# untitled.net
KiCad netlist of a schematic drawn in EAGLE
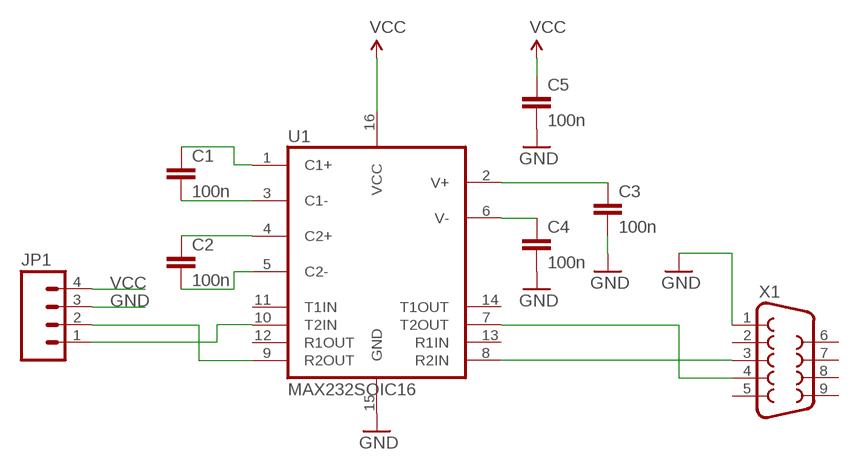
[diagram p0: schematic, sheet 1]

(export (version "E")
  (design (tool "Eeschema 10.0.6"))
  (components
    (comp (ref "C1")
      (value "100n")
      (footprint "eagle-import:1206")
      (libsource (lib "eagle-import") (part "CAP1206"))
    )
    (comp (ref "C2")
      (value "100n")
      (footprint "eagle-import:1206")
      (libsource (lib "eagle-import") (part "CAP1206"))
    )
    (comp (ref "C3")
      (value "100n")
      (footprint "eagle-import:1206")
      (libsource (lib "eagle-import") (part "CAP1206"))
    )
    (comp (ref "C4")
      (value "100n")
      (footprint "eagle-import:1206")
      (libsource (lib "eagle-import") (part "CAP1206"))
    )
    (comp (ref "C5")
      (value "100n")
      (footprint "eagle-import:1206")
      (libsource (lib "eagle-import") (part "CAP1206"))
    )
    (comp (ref "JP1")
      (value "M04PTH")
      (footprint "eagle-import:1X04")
      (libsource (lib "eagle-import") (part "M04PTH"))
    )
    (comp (ref "U1")
      (value "MAX232SOIC16")
      (footprint "eagle-import:SO016")
      (libsource (lib "eagle-import") (part "MAX232SOIC16"))
    )
    (comp (ref "X1")
      (value "DB9FEMALE")
      (footprint "eagle-import:DB9")
      (libsource (lib "eagle-import") (part "DB9FEMALE"))
    )
  )
  (nets
    (net (code "1") (name "GND") (class "Default")
      (node (ref "C3") (pin "2") (pinfunction "2_2") (pintype "passive"))
      (node (ref "C4") (pin "2") (pinfunction "2_2") (pintype "passive"))
      (node (ref "C5") (pin "2") (pinfunction "2_2") (pintype "passive"))
      (node (ref "JP1") (pin "3") (pinfunction "3_3") (pintype "passive"))
      (node (ref "U1") (pin "15") (pinfunction "GND_15") (pintype "bidirectional"))
      (node (ref "X1") (pin "1") (pinfunction "1_1") (pintype "passive"))
    )
    (net (code "2") (name "Net-(U1-C1+)") (class "Default")
      (node (ref "C1") (pin "1") (pinfunction "1_1") (pintype "passive"))
      (node (ref "U1") (pin "1") (pinfunction "C1+_1") (pintype "bidirectional"))
    )
    (net (code "3") (name "Net-(U1-C1-)") (class "Default")
      (node (ref "C1") (pin "2") (pinfunction "2_2") (pintype "passive"))
      (node (ref "U1") (pin "3") (pinfunction "C1-_3") (pintype "bidirectional"))
    )
    (net (code "4") (name "Net-(U1-C2+)") (class "Default")
      (node (ref "C2") (pin "1") (pinfunction "1_1") (pintype "passive"))
      (node (ref "U1") (pin "4") (pinfunction "C2+_4") (pintype "bidirectional"))
    )
    (net (code "5") (name "Net-(U1-C2-)") (class "Default")
      (node (ref "C2") (pin "2") (pinfunction "2_2") (pintype "passive"))
      (node (ref "U1") (pin "5") (pinfunction "C2-_5") (pintype "bidirectional"))
    )
    (net (code "6") (name "Net-(U1-R2IN)") (class "Default")
      (node (ref "U1") (pin "8") (pinfunction "R2IN_8") (pintype "input"))
      (node (ref "X1") (pin "3") (pinfunction "3_3") (pintype "passive"))
    )
    (net (code "7") (name "Net-(U1-R2OUT)") (class "Default")
      (node (ref "JP1") (pin "2") (pinfunction "2_2") (pintype "passive"))
      (node (ref "U1") (pin "9") (pinfunction "R2OUT_9") (pintype "output"))
    )
    (net (code "8") (name "Net-(U1-T2IN)") (class "Default")
      (node (ref "JP1") (pin "1") (pinfunction "1_1") (pintype "passive"))
      (node (ref "U1") (pin "10") (pinfunction "T2IN_10") (pintype "input"))
    )
    (net (code "9") (name "Net-(U1-T2OUT)") (class "Default")
      (node (ref "U1") (pin "7") (pinfunction "T2OUT_7") (pintype "output"))
      (node (ref "X1") (pin "4") (pinfunction "4_4") (pintype "passive"))
    )
    (net (code "10") (name "Net-(U1-V+)") (class "Default")
      (node (ref "C3") (pin "1") (pinfunction "1_1") (pintype "passive"))
      (node (ref "U1") (pin "2") (pinfunction "V+_2") (pintype "bidirectional"))
    )
    (net (code "11") (name "Net-(U1-V-)") (class "Default")
      (node (ref "C4") (pin "1") (pinfunction "1_1") (pintype "passive"))
      (node (ref "U1") (pin "6") (pinfunction "V-_6") (pintype "bidirectional"))
    )
    (net (code "12") (name "VCC") (class "Default")
      (node (ref "C5") (pin "1") (pinfunction "1_1") (pintype "passive"))
      (node (ref "JP1") (pin "4") (pinfunction "4_4") (pintype "passive"))
      (node (ref "U1") (pin "16") (pinfunction "VCC_16") (pintype "bidirectional"))
    )
    (net (code "13") (name "unconnected-(U1-R1IN-Pad13)") (class "Default")
      (node (ref "U1") (pin "13") (pinfunction "R1IN_13") (pintype "input"))
    )
    (net (code "14") (name "unconnected-(U1-R1OUT-Pad12)") (class "Default")
      (node (ref "U1") (pin "12") (pinfunction "R1OUT_12") (pintype "output"))
    )
    (net (code "15") (name "unconnected-(U1-T1IN-Pad11)") (class "Default")
      (node (ref "U1") (pin "11") (pinfunction "T1IN_11") (pintype "input"))
    )
    (net (code "16") (name "unconnected-(U1-T1OUT-Pad14)") (class "Default")
      (node (ref "U1") (pin "14") (pinfunction "T1OUT_14") (pintype "output"))
    )
    (net (code "17") (name "unconnected-(X1-Pad2)") (class "Default")
      (node (ref "X1") (pin "2") (pinfunction "2_2") (pintype "passive"))
    )
    (net (code "18") (name "unconnected-(X1-Pad5)") (class "Default")
      (node (ref "X1") (pin "5") (pinfunction "5_5") (pintype "passive"))
    )
    (net (code "19") (name "unconnected-(X1-Pad6)") (class "Default")
      (node (ref "X1") (pin "6") (pinfunction "6_6") (pintype "passive"))
    )
    (net (code "20") (name "unconnected-(X1-Pad7)") (class "Default")
      (node (ref "X1") (pin "7") (pinfunction "7_7") (pintype "passive"))
    )
    (net (code "21") (name "unconnected-(X1-Pad8)") (class "Default")
      (node (ref "X1") (pin "8") (pinfunction "8_8") (pintype "passive"))
    )
    (net (code "22") (name "unconnected-(X1-Pad9)") (class "Default")
      (node (ref "X1") (pin "9") (pinfunction "9_9") (pintype "passive"))
    )
  )
)
